# StaticPlatformADC_v1.net
KiCad netlist of a schematic drawn in EAGLE
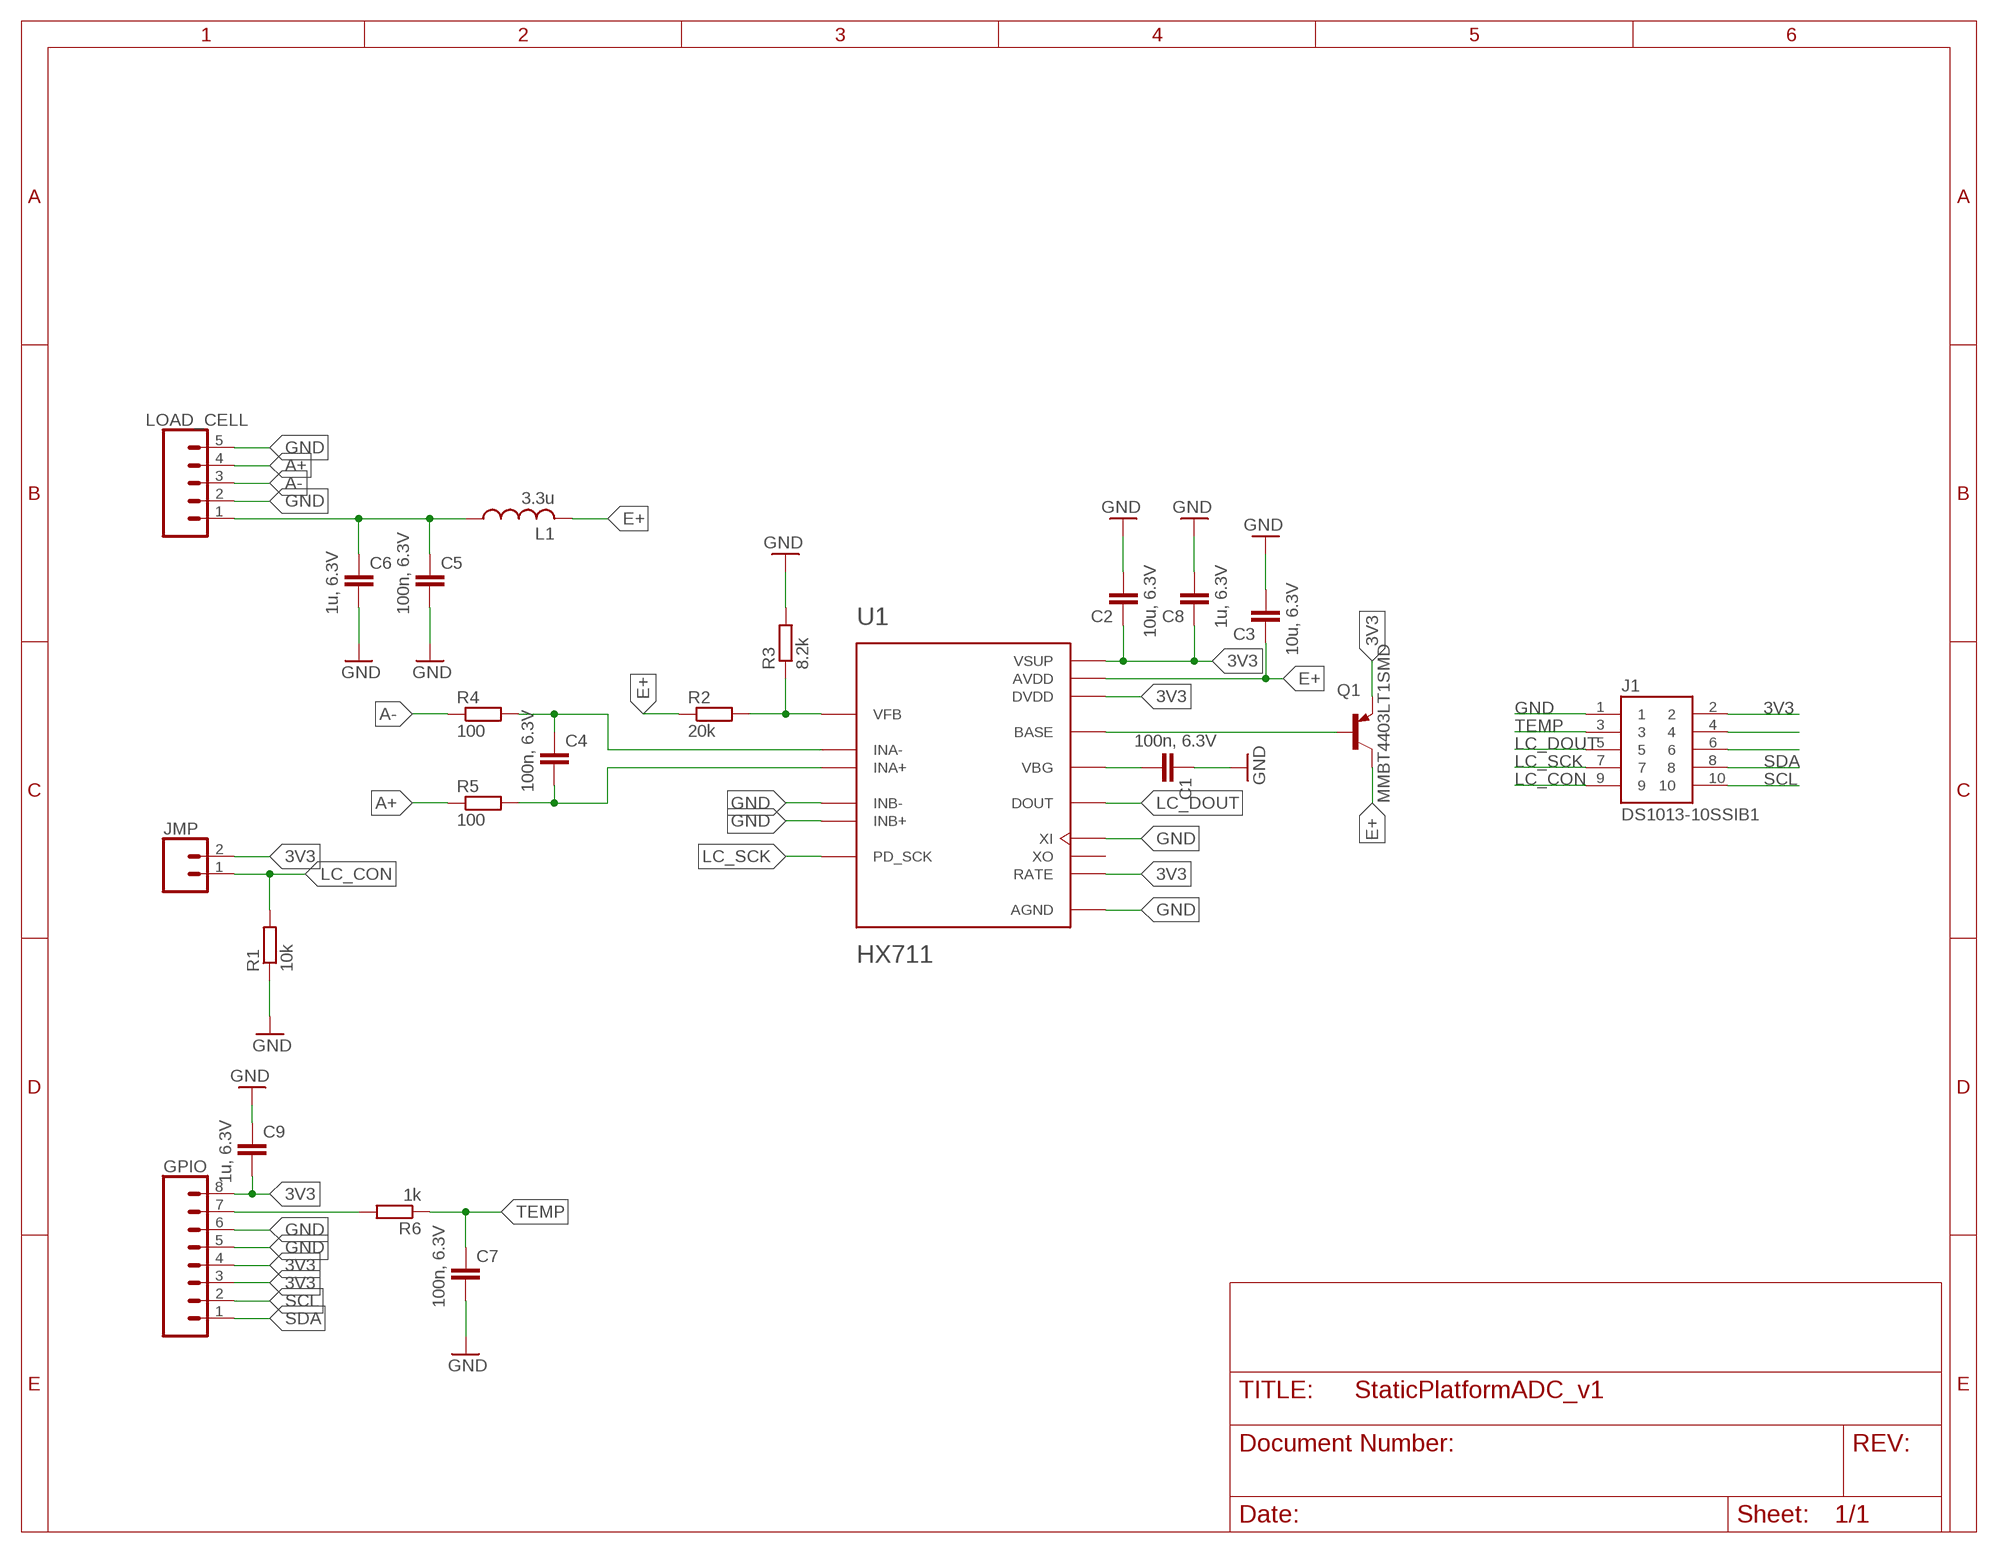
[diagram p0: schematic, sheet 1]

(export (version "E")
  (design (tool "Eeschema 10.0.6"))
  (components
    (comp (ref "C1")
      (value "100n, 6.3V")
      (footprint "eagle-import:C0805")
      (libsource (lib "eagle-import") (part "C-EUC0805"))
    )
    (comp (ref "C2")
      (value "10u, 6.3V")
      (footprint "eagle-import:C0805")
      (libsource (lib "eagle-import") (part "C-EUC0805"))
    )
    (comp (ref "C3")
      (value "10u, 6.3V")
      (footprint "eagle-import:C0805")
      (libsource (lib "eagle-import") (part "C-EUC0805"))
    )
    (comp (ref "C4")
      (value "100n, 6.3V")
      (footprint "eagle-import:C0805")
      (libsource (lib "eagle-import") (part "C-EUC0805"))
    )
    (comp (ref "C5")
      (value "100n, 6.3V")
      (footprint "eagle-import:C0805")
      (libsource (lib "eagle-import") (part "C-EUC0805"))
    )
    (comp (ref "C6")
      (value "1u, 6.3V")
      (footprint "eagle-import:C0805")
      (libsource (lib "eagle-import") (part "C-EUC0805"))
    )
    (comp (ref "C7")
      (value "100n, 6.3V")
      (footprint "eagle-import:C0805")
      (libsource (lib "eagle-import") (part "C-EUC0805"))
    )
    (comp (ref "C8")
      (value "1u, 6.3V")
      (footprint "eagle-import:C0805")
      (libsource (lib "eagle-import") (part "C-EUC0805"))
    )
    (comp (ref "C9")
      (value "1u, 6.3V")
      (footprint "eagle-import:C0805")
      (libsource (lib "eagle-import") (part "C-EUC0805"))
    )
    (comp (ref "GPIO")
      (value "CONN_08NO_SILK_FEMALE_PTH")
      (footprint "eagle-import:1X08_NO_SILK")
      (libsource (lib "eagle-import") (part "CONN_08NO_SILK_FEMALE_PTH"))
    )
    (comp (ref "J1")
      (value "DS1013-10SSIB1")
      (footprint "eagle-import:CONNFLY_DS1013-10SSIB1")
      (fields (field (name "MF") "Connfly"))
      (libsource (lib "eagle-import") (part "DS1013-10SSIB1"))
    )
    (comp (ref "JMP")
      (value "CONN_021X02_NO_SILK")
      (footprint "eagle-import:1X02_NO_SILK")
      (libsource (lib "eagle-import") (part "CONN_021X02_NO_SILK"))
    )
    (comp (ref "L1")
      (value "3.3u")
      (footprint "eagle-import:L3225P")
      (libsource (lib "eagle-import") (part "L-USL3225P"))
    )
    (comp (ref "LOAD_CELL")
      (value "CONN_05NO_SILK")
      (footprint "eagle-import:1X05_NO_SILK")
      (libsource (lib "eagle-import") (part "CONN_05NO_SILK"))
    )
    (comp (ref "Q1")
      (value "MMBT4403LT1SMD")
      (footprint "eagle-import:SOT23-BEC")
      (libsource (lib "eagle-import") (part "MMBT4403SMDLT1"))
    )
    (comp (ref "R1")
      (value "10k")
      (footprint "eagle-import:R0805")
      (libsource (lib "eagle-import") (part "R-EU_R0805"))
    )
    (comp (ref "R2")
      (value "20k")
      (footprint "eagle-import:R0805")
      (libsource (lib "eagle-import") (part "R-EU_R0805"))
    )
    (comp (ref "R3")
      (value "8.2k")
      (footprint "eagle-import:R0805")
      (libsource (lib "eagle-import") (part "R-EU_R0805"))
    )
    (comp (ref "R4")
      (value "100")
      (footprint "eagle-import:R0805")
      (libsource (lib "eagle-import") (part "R-EU_R0805"))
    )
    (comp (ref "R5")
      (value "100")
      (footprint "eagle-import:R0805")
      (libsource (lib "eagle-import") (part "R-EU_R0805"))
    )
    (comp (ref "R6")
      (value "1k")
      (footprint "eagle-import:R0805")
      (libsource (lib "eagle-import") (part "R-EU_R0805"))
    )
    (comp (ref "U1")
      (value "HX711")
      (footprint "eagle-import:SOP127P600X180-16N")
      (fields (field (name "MF") "AVIA SEMICONDUCTOR"))
      (libsource (lib "eagle-import") (part "HX711"))
    )
  )
  (nets
    (net (code "1") (name "3V3") (class "Default")
      (node (ref "C2") (pin "1") (pinfunction "1_1") (pintype "passive"))
      (node (ref "C8") (pin "1") (pinfunction "1_1") (pintype "passive"))
      (node (ref "C9") (pin "2") (pinfunction "2_2") (pintype "passive"))
      (node (ref "GPIO") (pin "3") (pinfunction "3_3") (pintype "passive"))
      (node (ref "GPIO") (pin "4") (pinfunction "4_4") (pintype "passive"))
      (node (ref "GPIO") (pin "8") (pinfunction "8_8") (pintype "passive"))
      (node (ref "J1") (pin "2") (pinfunction "2_2") (pintype "passive"))
      (node (ref "JMP") (pin "2") (pinfunction "2_2") (pintype "passive"))
      (node (ref "Q1") (pin "E") (pinfunction "E_E") (pintype "passive"))
      (node (ref "U1") (pin "1") (pinfunction "VSUP_1") (pintype "power_in"))
      (node (ref "U1") (pin "15") (pinfunction "RATE_15") (pintype "input"))
      (node (ref "U1") (pin "16") (pinfunction "DVDD_16") (pintype "power_in"))
    )
    (net (code "2") (name "A+") (class "Default")
      (node (ref "LOAD_CELL") (pin "4") (pinfunction "4_4") (pintype "passive"))
      (node (ref "R5") (pin "1") (pinfunction "1_1") (pintype "passive"))
    )
    (net (code "3") (name "A-") (class "Default")
      (node (ref "LOAD_CELL") (pin "3") (pinfunction "3_3") (pintype "passive"))
      (node (ref "R4") (pin "1") (pinfunction "1_1") (pintype "passive"))
    )
    (net (code "4") (name "E+") (class "Default")
      (node (ref "C3") (pin "1") (pinfunction "1_1") (pintype "passive"))
      (node (ref "L1") (pin "2") (pinfunction "2_2") (pintype "passive"))
      (node (ref "Q1") (pin "C") (pinfunction "C_C") (pintype "passive"))
      (node (ref "R2") (pin "1") (pinfunction "1_1") (pintype "passive"))
      (node (ref "U1") (pin "3") (pinfunction "AVDD_3") (pintype "power_in"))
    )
    (net (code "5") (name "GND") (class "Default")
      (node (ref "C1") (pin "1") (pinfunction "1_1") (pintype "passive"))
      (node (ref "C2") (pin "2") (pinfunction "2_2") (pintype "passive"))
      (node (ref "C3") (pin "2") (pinfunction "2_2") (pintype "passive"))
      (node (ref "C5") (pin "2") (pinfunction "2_2") (pintype "passive"))
      (node (ref "C6") (pin "2") (pinfunction "2_2") (pintype "passive"))
      (node (ref "C7") (pin "2") (pinfunction "2_2") (pintype "passive"))
      (node (ref "C8") (pin "2") (pinfunction "2_2") (pintype "passive"))
      (node (ref "C9") (pin "1") (pinfunction "1_1") (pintype "passive"))
      (node (ref "GPIO") (pin "5") (pinfunction "5_5") (pintype "passive"))
      (node (ref "GPIO") (pin "6") (pinfunction "6_6") (pintype "passive"))
      (node (ref "J1") (pin "1") (pinfunction "1_1") (pintype "passive"))
      (node (ref "LOAD_CELL") (pin "2") (pinfunction "2_2") (pintype "passive"))
      (node (ref "LOAD_CELL") (pin "5") (pinfunction "5_5") (pintype "passive"))
      (node (ref "R1") (pin "1") (pinfunction "1_1") (pintype "passive"))
      (node (ref "R3") (pin "2") (pinfunction "2_2") (pintype "passive"))
      (node (ref "U1") (pin "10") (pinfunction "INB+_10") (pintype "input"))
      (node (ref "U1") (pin "14") (pinfunction "XI_14") (pintype "input"))
      (node (ref "U1") (pin "5") (pinfunction "AGND_5") (pintype "power_in"))
      (node (ref "U1") (pin "9") (pinfunction "INB-_9") (pintype "input"))
    )
    (net (code "6") (name "LC_CON") (class "Default")
      (node (ref "J1") (pin "9") (pinfunction "9_9") (pintype "passive"))
      (node (ref "JMP") (pin "1") (pinfunction "1_1") (pintype "passive"))
      (node (ref "R1") (pin "2") (pinfunction "2_2") (pintype "passive"))
    )
    (net (code "7") (name "LC_DOUT") (class "Default")
      (node (ref "J1") (pin "5") (pinfunction "5_5") (pintype "passive"))
      (node (ref "U1") (pin "12") (pinfunction "DOUT_12") (pintype "output"))
    )
    (net (code "8") (name "LC_SCK") (class "Default")
      (node (ref "J1") (pin "7") (pinfunction "7_7") (pintype "passive"))
      (node (ref "U1") (pin "11") (pinfunction "PD_SCK_11") (pintype "input"))
    )
    (net (code "9") (name "Net-(C5-Pad1)") (class "Default")
      (node (ref "C5") (pin "1") (pinfunction "1_1") (pintype "passive"))
      (node (ref "C6") (pin "1") (pinfunction "1_1") (pintype "passive"))
      (node (ref "L1") (pin "1") (pinfunction "1_1") (pintype "passive"))
      (node (ref "LOAD_CELL") (pin "1") (pinfunction "1_1") (pintype "passive"))
    )
    (net (code "10") (name "Net-(GPIO-Pad7)") (class "Default")
      (node (ref "GPIO") (pin "7") (pinfunction "7_7") (pintype "passive"))
      (node (ref "R6") (pin "2") (pinfunction "2_2") (pintype "passive"))
    )
    (net (code "11") (name "Net-(U1-BASE)") (class "Default")
      (node (ref "Q1") (pin "B") (pinfunction "B_B") (pintype "passive"))
      (node (ref "U1") (pin "2") (pinfunction "BASE_2") (pintype "output"))
    )
    (net (code "12") (name "Net-(U1-INA+)") (class "Default")
      (node (ref "C4") (pin "2") (pinfunction "2_2") (pintype "passive"))
      (node (ref "R5") (pin "2") (pinfunction "2_2") (pintype "passive"))
      (node (ref "U1") (pin "8") (pinfunction "INA+_8") (pintype "input"))
    )
    (net (code "13") (name "Net-(U1-INA-)") (class "Default")
      (node (ref "C4") (pin "1") (pinfunction "1_1") (pintype "passive"))
      (node (ref "R4") (pin "2") (pinfunction "2_2") (pintype "passive"))
      (node (ref "U1") (pin "7") (pinfunction "INA-_7") (pintype "input"))
    )
    (net (code "14") (name "Net-(U1-VBG)") (class "Default")
      (node (ref "C1") (pin "2") (pinfunction "2_2") (pintype "passive"))
      (node (ref "U1") (pin "6") (pinfunction "VBG_6") (pintype "output"))
    )
    (net (code "15") (name "Net-(U1-VFB)") (class "Default")
      (node (ref "R2") (pin "2") (pinfunction "2_2") (pintype "passive"))
      (node (ref "R3") (pin "1") (pinfunction "1_1") (pintype "passive"))
      (node (ref "U1") (pin "4") (pinfunction "VFB_4") (pintype "input"))
    )
    (net (code "16") (name "SCL") (class "Default")
      (node (ref "GPIO") (pin "2") (pinfunction "2_2") (pintype "passive"))
      (node (ref "J1") (pin "10") (pinfunction "10_10") (pintype "passive"))
    )
    (net (code "17") (name "SDA") (class "Default")
      (node (ref "GPIO") (pin "1") (pinfunction "1_1") (pintype "passive"))
      (node (ref "J1") (pin "8") (pinfunction "8_8") (pintype "passive"))
    )
    (net (code "18") (name "TEMP") (class "Default")
      (node (ref "C7") (pin "1") (pinfunction "1_1") (pintype "passive"))
      (node (ref "J1") (pin "3") (pinfunction "3_3") (pintype "passive"))
      (node (ref "R6") (pin "1") (pinfunction "1_1") (pintype "passive"))
    )
    (net (code "19") (name "unconnected-(J1-Pad4)") (class "Default")
      (node (ref "J1") (pin "4") (pinfunction "4_4") (pintype "passive"))
    )
    (net (code "20") (name "unconnected-(J1-Pad6)") (class "Default")
      (node (ref "J1") (pin "6") (pinfunction "6_6") (pintype "passive"))
    )
    (net (code "21") (name "unconnected-(U1-XO-Pad13)") (class "Default")
      (node (ref "U1") (pin "13") (pinfunction "XO_13") (pintype "output"))
    )
  )
)
